# GPS.net
KiCad netlist of a schematic drawn in Altium Designer
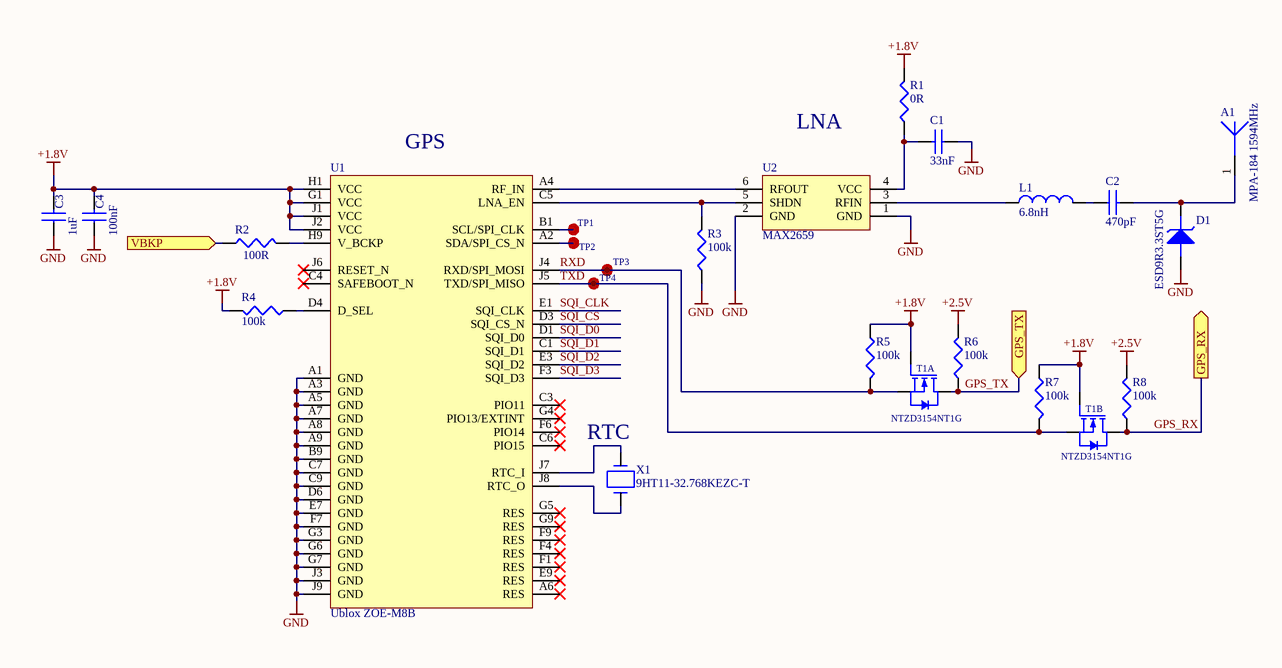
[diagram p0: GPS.SchDoc]

(export (version "E")
  (design (tool "Eeschema 10.0.6"))
  (components
    (comp (ref "A1")
      (value "MPA-184 1594MHz")
      (footprint "MPA-184")
      (description "Antennas Passive GPS/GLONASS Patch Antenna")
      (fields (field (name "MANUFACTURER") "Antenova") (field (name "MANUFACTURER PART NUMBER") "SR42I010-R"))
      (libsource (lib "Passive") (part "ANT - MAXTENA MPA-184 1594MHz"))
    )
    (comp (ref "C1")
      (value "33nF")
      (footprint "CAP0402")
      (fields
        (field (name "MANUFACTURER") "Multicomp")
        (field (name "MANUFACTURER PART NUMBER") "MC0402N330J160CT")
        (field (name "TOLERANCE") "5%")
      )
      (libsource (lib "Passive") (part "C - 33pF/0402"))
    )
    (comp (ref "C2")
      (value "470pF")
      (footprint "CAP0402")
      (fields
        (field (name "MANUFACTURER") "Murata")
        (field (name "MANUFACTURER PART NUMBER") "GRT155R71H471KE01D")
        (field (name "IRNAS PART NO.") "/")
      )
      (libsource (lib "Passive") (part "C - 470pF/0402"))
    )
    (comp (ref "C3")
      (value "1uF")
      (footprint "CAP0402")
      (description "CAP CER 1UF 10V 20% X5R 0402")
      (fields
        (field (name "MANUFACTURER") "Murata")
        (field (name "MANUFACTURER PART NUMBER") "GRM155R61A105ME15D")
      )
      (libsource (lib "Passive") (part "C - 1uF/0402"))
    )
    (comp (ref "C4")
      (value "100nF")
      (footprint "CAP0402")
      (fields
        (field (name "MANUFACTURER") "Multicomp")
        (field (name "MANUFACTURER PART NUMBER") "MC0402X104J160CT")
        (field (name "TOLERANCE") "5%")
      )
      (libsource (lib "Passive") (part "C - 100nF/0402"))
    )
    (comp (ref "D1")
      (value "ESD9R3.3ST5G")
      (footprint "SOD-923")
      (description "TVS Diode, ESD9R Series, Unidirectional, 3.3 V, 7.8 V")
      (fields
        (field (name "MANUFACTURER") "DIODES INC.")
        (field (name "MANUFACTURER PART NUMBER") "1N4148W-7-F.")
      )
      (libsource (lib "Active") (part "D_TVS - ESD9R3.3ST5G"))
    )
    (comp (ref "L1")
      (value "6.8nH")
      (footprint "IND0402")
      (description "FIXED IND 33NH 200MA 580 MOHM")
      (fields
        (field (name "MANUFACTURER") "Murata")
        (field (name "MANUFACTURER PART NUMBER") "LQG15HS33NJ02D")
      )
      (libsource (lib "Passive") (part "L - 33nH/0402"))
    )
    (comp (ref "R1")
      (value "0R")
      (footprint "RES0402")
      (description "RESISTOR, 0402, 0R, ANTI SULFURATION")
      (fields
        (field (name "MANUFACTURER") "Multicomp")
        (field (name "MANUFACTURER PART NUMBER") "MCMR04X000PTL")
      )
      (libsource (lib "Passive") (part "R - 0R/0402"))
    )
    (comp (ref "R2")
      (value "100R")
      (footprint "RES0402")
      (fields
        (field (name "MANUFACTURER") "Multicomp")
        (field (name "MANUFACTURER PART NUMBER") "MCMR04X1000FTL")
        (field (name "TOLERANCE") "1%")
      )
      (libsource (lib "Passive") (part "R - 100R/0402"))
    )
    (comp (ref "R3")
      (value "100k")
      (footprint "RES0402")
      (description "MULTICOMP   MCWR04X1003FTL   RES, THICK FILM, 100KOHM, 1%, 0.0625W")
      (fields
        (field (name "MANUFACTURER") "Multicomp")
        (field (name "MANUFACTURER PART NUMBER") "MCWR04X1003FTL")
      )
      (libsource (lib "Passive") (part "R - 100k/0402"))
    )
    (comp (ref "R4")
      (value "100k")
      (footprint "RES0402")
      (description "MULTICOMP   MCWR04X1003FTL   RES, THICK FILM, 100KOHM, 1%, 0.0625W")
      (fields
        (field (name "MANUFACTURER") "Multicomp")
        (field (name "MANUFACTURER PART NUMBER") "MCWR04X1003FTL")
      )
      (libsource (lib "Passive") (part "R - 100k/0402"))
    )
    (comp (ref "R5")
      (value "100k")
      (footprint "RES0402")
      (description "MULTICOMP   MCWR04X1003FTL   RES, THICK FILM, 100KOHM, 1%, 0.0625W")
      (fields
        (field (name "MANUFACTURER") "Multicomp")
        (field (name "MANUFACTURER PART NUMBER") "MCWR04X1003FTL")
      )
      (libsource (lib "Passive") (part "R - 100k/0402"))
    )
    (comp (ref "R6")
      (value "100k")
      (footprint "RES0402")
      (description "MULTICOMP   MCWR04X1003FTL   RES, THICK FILM, 100KOHM, 1%, 0.0625W")
      (fields
        (field (name "MANUFACTURER") "Multicomp")
        (field (name "MANUFACTURER PART NUMBER") "MCWR04X1003FTL")
      )
      (libsource (lib "Passive") (part "R - 100k/0402"))
    )
    (comp (ref "R7")
      (value "100k")
      (footprint "RES0402")
      (description "MULTICOMP   MCWR04X1003FTL   RES, THICK FILM, 100KOHM, 1%, 0.0625W")
      (fields
        (field (name "MANUFACTURER") "Multicomp")
        (field (name "MANUFACTURER PART NUMBER") "MCWR04X1003FTL")
      )
      (libsource (lib "Passive") (part "R - 100k/0402"))
    )
    (comp (ref "R8")
      (value "100k")
      (footprint "RES0402")
      (description "MULTICOMP   MCWR04X1003FTL   RES, THICK FILM, 100KOHM, 1%, 0.0625W")
      (fields
        (field (name "MANUFACTURER") "Multicomp")
        (field (name "MANUFACTURER PART NUMBER") "MCWR04X1003FTL")
      )
      (libsource (lib "Passive") (part "R - 100k/0402"))
    )
    (comp (ref "T1")
      (value "NTZD3154NT1G")
      (footprint "SOT-563")
      (description "Dual MOSFET, Dual N Channel, 540 mA, 20 V, 0.4 ohm, 4.5 V, 1 V")
      (fields (field (name "AUTHOR") "Ciril Golob"))
      (libsource (lib "Active") (part "T_M - NTZD3154NT1G"))
    )
    (comp (ref "TP1")
      (value "TestPoint")
      (footprint "Passive:TestPoint:1.2x1.2mm")
      (description "TEST POINT ROUND SMD")
      (libsource (lib "Passive") (part "TestPoint"))
    )
    (comp (ref "TP2")
      (value "TestPoint")
      (footprint "Passive:TestPoint:1.2x1.2mm")
      (description "TEST POINT ROUND SMD")
      (libsource (lib "Passive") (part "TestPoint"))
    )
    (comp (ref "TP3")
      (value "TestPoint")
      (footprint "Passive:TestPoint:1.2x1.2mm")
      (description "TEST POINT ROUND SMD")
      (libsource (lib "Passive") (part "TestPoint"))
    )
    (comp (ref "TP4")
      (value "TestPoint")
      (footprint "Passive:TestPoint:1.2x1.2mm")
      (description "TEST POINT ROUND SMD")
      (libsource (lib "Passive") (part "TestPoint"))
    )
    (comp (ref "U1")
      (value "Ublox ZOE-M8B")
      (footprint "S-LGA51")
      (description "ZOE-M8 RF Receiver BeiDou, Galileo, GLONASS, GNSS, GPS -160dBm")
      (fields (field (name "MANUFACTURER") "u-blox") (field (name "MANUFACTURER PART NUMBER") "MAX-M8Q-0"))
      (libsource (lib "Active") (part "RF - UBLOX-ZOE-M8B"))
    )
    (comp (ref "U2")
      (value "MAX2659")
      (footprint "uDFN-6")
      (description "RF Amplifier, GPS / GNSS, 20.5 dB Gain / 0.8 dB Noise, 1575.42 MHz, 1.6 V to 3.3 V Supply")
      (fields (field (name "MANUFACTURER") "u-blox") (field (name "MANUFACTURER PART NUMBER") "MAX-M8Q-0"))
      (libsource (lib "Active") (part "RF - MAX2659"))
    )
    (comp (ref "X1")
      (value "9HT11-32.768KEZC-T")
      (footprint "9HT11")
      (description "Crystal, 32.768 kHz, SMD, 2mm x 1.2mm, 9 pF, 10 ppm, 9HT11 Series")
      (fields (field (name "MANUFACTURER") "IQD") (field (name "MANUFACTURER PART NUMBER") "LFXTAL009678"))
      (libsource (lib "Passive") (part "X - 9HT11-32.768KEZC-T"))
    )
  )
  (nets
    (net (code "1") (name "+1.8V") (class "Default")
      (node (ref "C3") (pin "2") (pinfunction "2_2") (pintype "passive"))
      (node (ref "C4") (pin "2") (pinfunction "2_2") (pintype "passive"))
      (node (ref "R1") (pin "2") (pinfunction "2_2") (pintype "passive"))
      (node (ref "R4") (pin "2") (pinfunction "2_2") (pintype "passive"))
      (node (ref "R5") (pin "1") (pinfunction "1_1") (pintype "passive"))
      (node (ref "R7") (pin "1") (pinfunction "1_1") (pintype "passive"))
      (node (ref "T1") (pin "2") (pinfunction "G1_2") (pintype "passive"))
      (node (ref "T1") (pin "5") (pinfunction "G2_5") (pintype "passive"))
      (node (ref "U1") (pin "G1") (pinfunction "VCC_G1") (pintype "passive"))
      (node (ref "U1") (pin "H1") (pinfunction "VCC_H1") (pintype "passive"))
      (node (ref "U1") (pin "J1") (pinfunction "VCC_J1") (pintype "passive"))
      (node (ref "U1") (pin "J2") (pinfunction "VCC_J2") (pintype "passive"))
    )
    (net (code "2") (name "+2.5V") (class "Default")
      (node (ref "R6") (pin "2") (pinfunction "2_2") (pintype "passive"))
      (node (ref "R8") (pin "2") (pinfunction "2_2") (pintype "passive"))
    )
    (net (code "3") (name "/GPS_RX") (class "Default")
      (node (ref "R8") (pin "1") (pinfunction "1_1") (pintype "passive"))
      (node (ref "T1") (pin "3") (pinfunction "D2_3") (pintype "passive"))
    )
    (net (code "4") (name "/GPS_TX") (class "Default")
      (node (ref "R6") (pin "1") (pinfunction "1_1") (pintype "passive"))
      (node (ref "T1") (pin "6") (pinfunction "D1_6") (pintype "passive"))
    )
    (net (code "5") (name "/RXD") (class "Default")
      (node (ref "R5") (pin "2") (pinfunction "2_2") (pintype "passive"))
      (node (ref "T1") (pin "1") (pinfunction "S1_1") (pintype "passive"))
      (node (ref "TP3") (pin "0") (pinfunction "0_0") (pintype "passive"))
      (node (ref "U1") (pin "J4") (pinfunction "RXD/SPI_MOSI_J4") (pintype "passive"))
    )
    (net (code "6") (name "/SQI_CLK") (class "Default")
      (node (ref "U1") (pin "E1") (pinfunction "SQI_CLK_E1") (pintype "passive"))
    )
    (net (code "7") (name "/SQI_CS") (class "Default")
      (node (ref "U1") (pin "D3") (pinfunction "SQI_CS_N_D3") (pintype "passive"))
    )
    (net (code "8") (name "/SQI_D0") (class "Default")
      (node (ref "U1") (pin "D1") (pinfunction "SQI_D0_D1") (pintype "passive"))
    )
    (net (code "9") (name "/SQI_D1") (class "Default")
      (node (ref "U1") (pin "C1") (pinfunction "SQI_D1_C1") (pintype "passive"))
    )
    (net (code "10") (name "/SQI_D2") (class "Default")
      (node (ref "U1") (pin "E3") (pinfunction "SQI_D2_E3") (pintype "passive"))
    )
    (net (code "11") (name "/SQI_D3") (class "Default")
      (node (ref "U1") (pin "F3") (pinfunction "SQI_D3_F3") (pintype "passive"))
    )
    (net (code "12") (name "/TXD") (class "Default")
      (node (ref "R7") (pin "2") (pinfunction "2_2") (pintype "passive"))
      (node (ref "T1") (pin "4") (pinfunction "S2_4") (pintype "passive"))
      (node (ref "TP4") (pin "0") (pinfunction "0_0") (pintype "passive"))
      (node (ref "U1") (pin "J5") (pinfunction "TXD/SPI_MISO_J5") (pintype "passive"))
    )
    (net (code "13") (name "/VBKP") (class "Default")
      (node (ref "R2") (pin "1") (pinfunction "1_1") (pintype "passive"))
    )
    (net (code "14") (name "GND") (class "Default")
      (node (ref "C1") (pin "1") (pinfunction "1_1") (pintype "passive"))
      (node (ref "C3") (pin "1") (pinfunction "1_1") (pintype "passive"))
      (node (ref "C4") (pin "1") (pinfunction "1_1") (pintype "passive"))
      (node (ref "D1") (pin "A") (pinfunction "ANODE_A") (pintype "passive"))
      (node (ref "R3") (pin "1") (pinfunction "1_1") (pintype "passive"))
      (node (ref "U1") (pin "A1") (pinfunction "GND_A1") (pintype "passive"))
      (node (ref "U1") (pin "A3") (pinfunction "GND_A3") (pintype "passive"))
      (node (ref "U1") (pin "A5") (pinfunction "GND_A5") (pintype "passive"))
      (node (ref "U1") (pin "A7") (pinfunction "GND_A7") (pintype "passive"))
      (node (ref "U1") (pin "A8") (pinfunction "GND_A8") (pintype "passive"))
      (node (ref "U1") (pin "A9") (pinfunction "GND_A9") (pintype "passive"))
      (node (ref "U1") (pin "B9") (pinfunction "GND_B9") (pintype "passive"))
      (node (ref "U1") (pin "C7") (pinfunction "GND_C7") (pintype "passive"))
      (node (ref "U1") (pin "C9") (pinfunction "GND_C9") (pintype "passive"))
      (node (ref "U1") (pin "D6") (pinfunction "GND_D6") (pintype "passive"))
      (node (ref "U1") (pin "E7") (pinfunction "GND_E7") (pintype "passive"))
      (node (ref "U1") (pin "F7") (pinfunction "GND_F7") (pintype "passive"))
      (node (ref "U1") (pin "G3") (pinfunction "GND_G3") (pintype "passive"))
      (node (ref "U1") (pin "G6") (pinfunction "GND_G6") (pintype "passive"))
      (node (ref "U1") (pin "G7") (pinfunction "GND_G7") (pintype "passive"))
      (node (ref "U1") (pin "J3") (pinfunction "GND_J3") (pintype "passive"))
      (node (ref "U1") (pin "J9") (pinfunction "GND_J9") (pintype "passive"))
      (node (ref "U2") (pin "1") (pinfunction "GND_1") (pintype "passive"))
      (node (ref "U2") (pin "2") (pinfunction "GND_2") (pintype "passive"))
    )
    (net (code "15") (name "Net-(A1-ANT)") (class "Default")
      (node (ref "A1") (pin "1") (pinfunction "ANT_1") (pintype "passive"))
      (node (ref "C2") (pin "2") (pinfunction "2_2") (pintype "passive"))
      (node (ref "D1") (pin "K") (pinfunction "cathode_K") (pintype "passive"))
    )
    (net (code "16") (name "Net-(C2-Pad1)") (class "Default")
      (node (ref "C2") (pin "1") (pinfunction "1_1") (pintype "passive"))
      (node (ref "L1") (pin "2") (pinfunction "2_2") (pintype "passive"))
    )
    (net (code "17") (name "Net-(U1-D_SEL)") (class "Default")
      (node (ref "R4") (pin "1") (pinfunction "1_1") (pintype "passive"))
      (node (ref "U1") (pin "D4") (pinfunction "D_SEL_D4") (pintype "passive"))
    )
    (net (code "18") (name "Net-(U1-LNA_EN)") (class "Default")
      (node (ref "R3") (pin "2") (pinfunction "2_2") (pintype "passive"))
      (node (ref "U1") (pin "C5") (pinfunction "LNA_EN_C5") (pintype "passive"))
      (node (ref "U2") (pin "5") (pinfunction "SHDN_5") (pintype "passive"))
    )
    (net (code "19") (name "Net-(U1-RF_IN)") (class "Default")
      (node (ref "U1") (pin "A4") (pinfunction "RF_IN_A4") (pintype "passive"))
      (node (ref "U2") (pin "6") (pinfunction "RFOUT_6") (pintype "passive"))
    )
    (net (code "20") (name "Net-(U1-RTC_I)") (class "Default")
      (node (ref "U1") (pin "J7") (pinfunction "RTC_I_J7") (pintype "passive"))
      (node (ref "X1") (pin "2") (pinfunction "2_2") (pintype "passive"))
    )
    (net (code "21") (name "Net-(U1-RTC_O)") (class "Default")
      (node (ref "U1") (pin "J8") (pinfunction "RTC_O_J8") (pintype "passive"))
      (node (ref "X1") (pin "1") (pinfunction "1_1") (pintype "passive"))
    )
    (net (code "22") (name "Net-(U1-SCL{slash}SPI_CLK)") (class "Default")
      (node (ref "TP1") (pin "0") (pinfunction "0_0") (pintype "passive"))
      (node (ref "U1") (pin "B1") (pinfunction "SCL/SPI_CLK_B1") (pintype "passive"))
    )
    (net (code "23") (name "Net-(U1-SDA{slash}SPI_CS_N)") (class "Default")
      (node (ref "TP2") (pin "0") (pinfunction "0_0") (pintype "passive"))
      (node (ref "U1") (pin "A2") (pinfunction "SDA/SPI_CS_N_A2") (pintype "passive"))
    )
    (net (code "24") (name "Net-(U1-V_BCKP)") (class "Default")
      (node (ref "R2") (pin "2") (pinfunction "2_2") (pintype "passive"))
      (node (ref "U1") (pin "H9") (pinfunction "V_BCKP_H9") (pintype "passive"))
    )
    (net (code "25") (name "Net-(U2-RFIN)") (class "Default")
      (node (ref "L1") (pin "1") (pinfunction "1_1") (pintype "passive"))
      (node (ref "U2") (pin "3") (pinfunction "RFIN_3") (pintype "passive"))
    )
    (net (code "26") (name "Net-(U2-VCC)") (class "Default")
      (node (ref "C1") (pin "2") (pinfunction "2_2") (pintype "passive"))
      (node (ref "R1") (pin "1") (pinfunction "1_1") (pintype "passive"))
      (node (ref "U2") (pin "4") (pinfunction "VCC_4") (pintype "passive"))
    )
    (net (code "27") (name "unconnected-(U1-PIO11-PadC3)") (class "Default")
      (node (ref "U1") (pin "C3") (pinfunction "PIO11_C3") (pintype "passive+no_connect"))
    )
    (net (code "28") (name "unconnected-(U1-PIO13{slash}EXTINT-PadG4)") (class "Default")
      (node (ref "U1") (pin "G4") (pinfunction "PIO13/EXTINT_G4") (pintype "passive+no_connect"))
    )
    (net (code "29") (name "unconnected-(U1-PIO14-PadF6)") (class "Default")
      (node (ref "U1") (pin "F6") (pinfunction "PIO14_F6") (pintype "passive+no_connect"))
    )
    (net (code "30") (name "unconnected-(U1-PIO15-PadC6)") (class "Default")
      (node (ref "U1") (pin "C6") (pinfunction "PIO15_C6") (pintype "passive+no_connect"))
    )
    (net (code "31") (name "unconnected-(U1-RES-PadA6)") (class "Default")
      (node (ref "U1") (pin "A6") (pinfunction "RES_A6") (pintype "passive+no_connect"))
    )
    (net (code "32") (name "unconnected-(U1-RES-PadE9)") (class "Default")
      (node (ref "U1") (pin "E9") (pinfunction "RES_E9") (pintype "passive+no_connect"))
    )
    (net (code "33") (name "unconnected-(U1-RES-PadF1)") (class "Default")
      (node (ref "U1") (pin "F1") (pinfunction "RES_F1") (pintype "passive+no_connect"))
    )
    (net (code "34") (name "unconnected-(U1-RES-PadF4)") (class "Default")
      (node (ref "U1") (pin "F4") (pinfunction "RES_F4") (pintype "passive+no_connect"))
    )
    (net (code "35") (name "unconnected-(U1-RES-PadF9)") (class "Default")
      (node (ref "U1") (pin "F9") (pinfunction "RES_F9") (pintype "passive+no_connect"))
    )
    (net (code "36") (name "unconnected-(U1-RES-PadG5)") (class "Default")
      (node (ref "U1") (pin "G5") (pinfunction "RES_G5") (pintype "passive+no_connect"))
    )
    (net (code "37") (name "unconnected-(U1-RES-PadG9)") (class "Default")
      (node (ref "U1") (pin "G9") (pinfunction "RES_G9") (pintype "passive+no_connect"))
    )
    (net (code "38") (name "unconnected-(U1-RESET_N-PadJ6)") (class "Default")
      (node (ref "U1") (pin "J6") (pinfunction "RESET_N_J6") (pintype "passive+no_connect"))
    )
    (net (code "39") (name "unconnected-(U1-SAFEBOOT_N-PadC4)") (class "Default")
      (node (ref "U1") (pin "C4") (pinfunction "SAFEBOOT_N_C4") (pintype "passive+no_connect"))
    )
  )
)
